# Distance-Sensors.net
KiCad netlist of a schematic drawn in Altium Designer
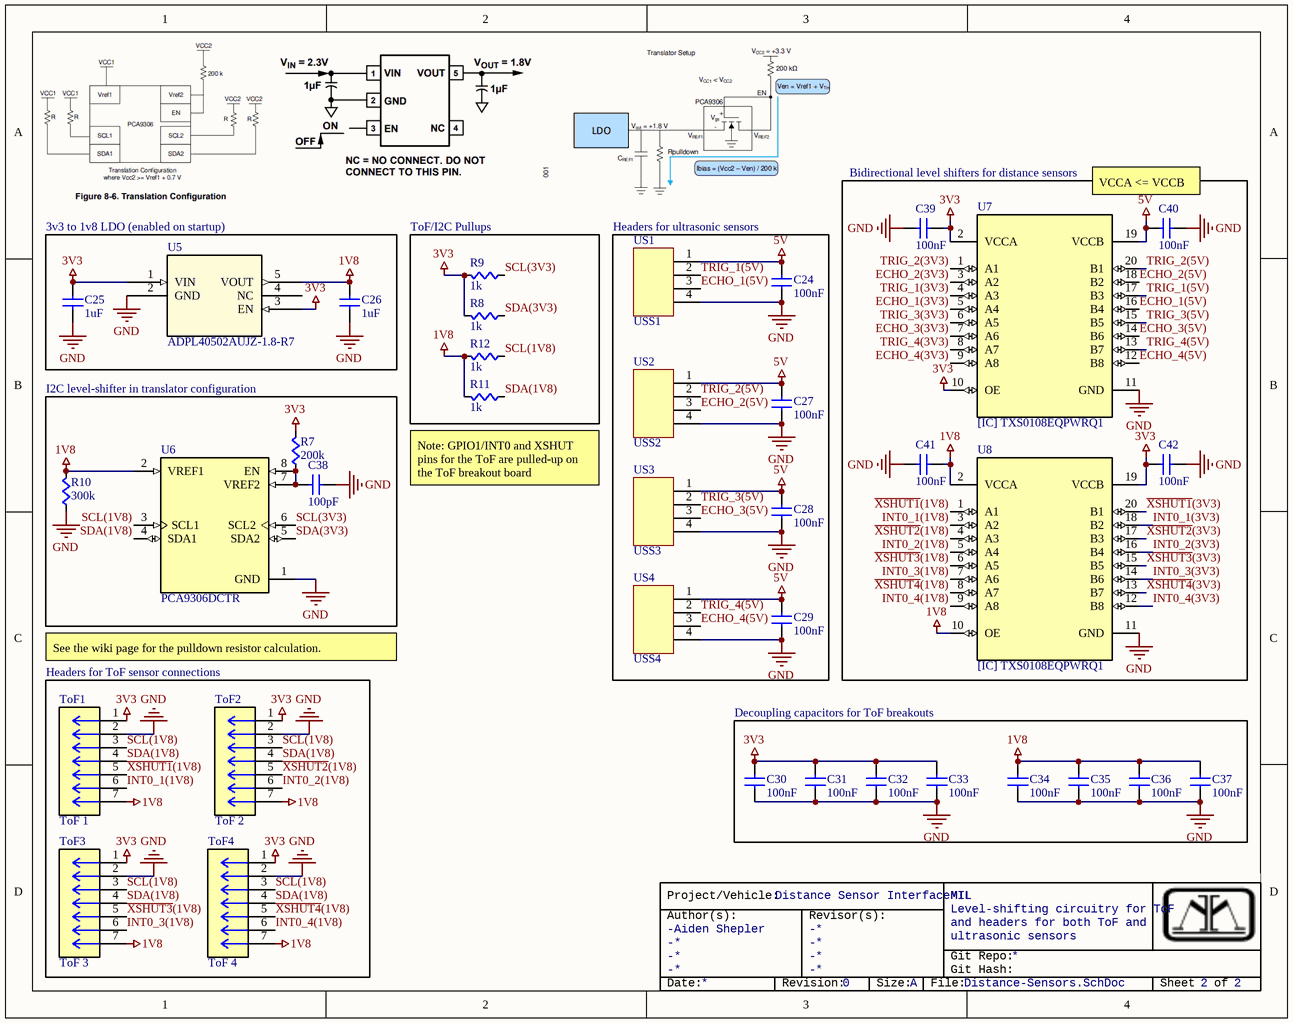
[diagram p0: Distance-Sensors.SchDoc]

(export (version "E")
  (design (tool "Eeschema 10.0.6"))
  (components
    (comp (ref "C24")
      (value "100nF")
      (footprint "CAPC0603")
      (fields (field (name "Comment") "Cap"))
      (libsource (lib "Passives") (part "Cap"))
    )
    (comp (ref "C25")
      (value "1uF")
      (footprint "CAPC0603")
      (fields (field (name "Comment") "Cap"))
      (libsource (lib "Passives") (part "Cap"))
    )
    (comp (ref "C26")
      (value "1uF")
      (footprint "CAPC0603")
      (fields (field (name "Comment") "Cap"))
      (libsource (lib "Passives") (part "Cap"))
    )
    (comp (ref "C27")
      (value "100nF")
      (footprint "CAPC0603")
      (fields (field (name "Comment") "Cap"))
      (libsource (lib "Passives") (part "Cap"))
    )
    (comp (ref "C28")
      (value "100nF")
      (footprint "CAPC0603")
      (fields (field (name "Comment") "Cap"))
      (libsource (lib "Passives") (part "Cap"))
    )
    (comp (ref "C29")
      (value "100nF")
      (footprint "CAPC0603")
      (fields (field (name "Comment") "Cap"))
      (libsource (lib "Passives") (part "Cap"))
    )
    (comp (ref "C30")
      (value "100nF")
      (footprint "CAPC0603")
      (fields (field (name "Comment") "Cap"))
      (libsource (lib "Passives") (part "Cap"))
    )
    (comp (ref "C31")
      (value "100nF")
      (footprint "CAPC0603")
      (fields (field (name "Comment") "Cap"))
      (libsource (lib "Passives") (part "Cap"))
    )
    (comp (ref "C32")
      (value "100nF")
      (footprint "CAPC0603")
      (fields (field (name "Comment") "Cap"))
      (libsource (lib "Passives") (part "Cap"))
    )
    (comp (ref "C33")
      (value "100nF")
      (footprint "CAPC0603")
      (fields (field (name "Comment") "Cap"))
      (libsource (lib "Passives") (part "Cap"))
    )
    (comp (ref "C34")
      (value "100nF")
      (footprint "CAPC0603")
      (fields (field (name "Comment") "Cap"))
      (libsource (lib "Passives") (part "Cap"))
    )
    (comp (ref "C35")
      (value "100nF")
      (footprint "CAPC0603")
      (fields (field (name "Comment") "Cap"))
      (libsource (lib "Passives") (part "Cap"))
    )
    (comp (ref "C36")
      (value "100nF")
      (footprint "CAPC0603")
      (fields (field (name "Comment") "Cap"))
      (libsource (lib "Passives") (part "Cap"))
    )
    (comp (ref "C37")
      (value "100nF")
      (footprint "CAPC0603")
      (fields (field (name "Comment") "Cap"))
      (libsource (lib "Passives") (part "Cap"))
    )
    (comp (ref "C38")
      (value "100pF")
      (footprint "CAPC0603")
      (fields (field (name "Comment") "Cap"))
      (libsource (lib "Passives") (part "Cap"))
    )
    (comp (ref "C39")
      (value "100nF")
      (footprint "CAPC0603")
      (fields (field (name "Comment") "Cap"))
      (libsource (lib "Passives") (part "Cap"))
    )
    (comp (ref "C40")
      (value "100nF")
      (footprint "CAPC0603")
      (fields (field (name "Comment") "Cap"))
      (libsource (lib "Passives") (part "Cap"))
    )
    (comp (ref "C41")
      (value "100nF")
      (footprint "CAPC0603")
      (fields (field (name "Comment") "Cap"))
      (libsource (lib "Passives") (part "Cap"))
    )
    (comp (ref "C42")
      (value "100nF")
      (footprint "CAPC0603")
      (fields (field (name "Comment") "Cap"))
      (libsource (lib "Passives") (part "Cap"))
    )
    (comp (ref "R7")
      (value "200k")
      (footprint "RES0603")
      (description "SMD, RES0603")
      (fields (field (name "Comment") "Res"))
      (libsource (lib "Passives") (part "Res"))
    )
    (comp (ref "R8")
      (value "1k")
      (footprint "RES0603")
      (description "SMD, RES0603")
      (fields (field (name "Comment") "Res"))
      (libsource (lib "Passives") (part "Res"))
    )
    (comp (ref "R9")
      (value "1k")
      (footprint "RES0603")
      (description "SMD, RES0603")
      (fields (field (name "Comment") "Res"))
      (libsource (lib "Passives") (part "Res"))
    )
    (comp (ref "R10")
      (value "300k")
      (footprint "RES0603")
      (description "SMD, RES0603")
      (fields (field (name "Comment") "Res"))
      (libsource (lib "Passives") (part "Res"))
    )
    (comp (ref "R11")
      (value "1k")
      (footprint "RES0603")
      (description "SMD, RES0603")
      (fields (field (name "Comment") "Res"))
      (libsource (lib "Passives") (part "Res"))
    )
    (comp (ref "R12")
      (value "1k")
      (footprint "RES0603")
      (description "SMD, RES0603")
      (fields (field (name "Comment") "Res"))
      (libsource (lib "Passives") (part "Res"))
    )
    (comp (ref "ToF1")
      (value "ToF 1")
      (footprint "7POS_2MM_CONN")
      (description "1x7 2mm pitch sherlock connector")
      (fields (field (name "MP") "353620750"))
      (libsource (lib "353620750") (part "MOLEX_SHERLOCK_1x7_CONN"))
    )
    (comp (ref "ToF2")
      (value "ToF 2")
      (footprint "7POS_2MM_CONN")
      (description "1x7 2mm pitch sherlock connector")
      (fields (field (name "MP") "353620750"))
      (libsource (lib "353620750") (part "MOLEX_SHERLOCK_1x7_CONN"))
    )
    (comp (ref "ToF3")
      (value "ToF 3")
      (footprint "7POS_2MM_CONN")
      (description "1x7 2mm pitch sherlock connector")
      (fields (field (name "MP") "353620750"))
      (libsource (lib "353620750") (part "MOLEX_SHERLOCK_1x7_CONN"))
    )
    (comp (ref "ToF4")
      (value "ToF 4")
      (footprint "7POS_2MM_CONN")
      (description "1x7 2mm pitch sherlock connector")
      (fields (field (name "MP") "353620750"))
      (libsource (lib "353620750") (part "MOLEX_SHERLOCK_1x7_CONN"))
    )
    (comp (ref "U5")
      (value "ADPL40502AUJZ-1.8-R7")
      (footprint "TSOT-23-5_UJ-5_ADI")
      (description "Low Noise, 200mA, CMOS Linear Regulator (LDO)")
      (fields (field (name "COPYRIGHT") "Copyright (C) 2025 Ultra Librarian. All rights reserved."))
      (libsource (lib "Alexandria") (part "ADPL40502AUJZ-1.8-R7"))
    )
    (comp (ref "U6")
      (value "PCA9306DCTR")
      (footprint "SOP65P400X130-8N")
      (description "2-bit bidirectional 400-kHz I2C/SMBus voltage level translator")
      (fields (field (name "MF") "Texas Instruments"))
      (libsource (lib "Alexandria") (part "PCA9306DCTR"))
    )
    (comp (ref "U7")
      (value "[IC] TXS0108EQPWRQ1")
      (footprint "SOP65P640X120-20N")
      (description "Automotive eight-bit bidirectional voltage level shifter for open-drain and push-pull applications")
      (fields (field (name "MF") "Texas Instruments") (field (name "MP") "TXS0108EQPWRQ1"))
      (libsource (lib "Alexandria") (part "[IC] TXS0108EQPWRQ1"))
    )
    (comp (ref "U8")
      (value "[IC] TXS0108EQPWRQ1")
      (footprint "SOP65P640X120-20N")
      (description "Automotive eight-bit bidirectional voltage level shifter for open-drain and push-pull applications")
      (fields (field (name "MF") "Texas Instruments") (field (name "MP") "TXS0108EQPWRQ1"))
      (libsource (lib "Alexandria") (part "[IC] TXS0108EQPWRQ1"))
    )
    (comp (ref "US1")
      (value "USS1")
      (footprint "MOLEX-HDR-1X4-SHERLOCK-VERT")
      (libsource (lib "Connectors") (part "MOLEX-HDR-1x4-SHERLOCK_VERT"))
    )
    (comp (ref "US2")
      (value "USS2")
      (footprint "MOLEX-HDR-1X4-SHERLOCK-VERT")
      (libsource (lib "Connectors") (part "MOLEX-HDR-1x4-SHERLOCK_VERT"))
    )
    (comp (ref "US3")
      (value "USS3")
      (footprint "MOLEX-HDR-1X4-SHERLOCK-VERT")
      (libsource (lib "Connectors") (part "MOLEX-HDR-1x4-SHERLOCK_VERT"))
    )
    (comp (ref "US4")
      (value "USS4")
      (footprint "MOLEX-HDR-1X4-SHERLOCK-VERT")
      (libsource (lib "Connectors") (part "MOLEX-HDR-1x4-SHERLOCK_VERT"))
    )
  )
  (nets
    (net (code "1") (name "/ECHO_1(3V3)") (class "Default")
      (node (ref "U7") (pin "5") (pinfunction "A4_5") (pintype "bidirectional"))
    )
    (net (code "2") (name "/ECHO_1(5V)") (class "Default")
      (node (ref "U7") (pin "16") (pinfunction "B4_16") (pintype "bidirectional"))
      (node (ref "US1") (pin "3") (pinfunction "3_3") (pintype "passive"))
    )
    (net (code "3") (name "/ECHO_2(3V3)") (class "Default")
      (node (ref "U7") (pin "3") (pinfunction "A2_3") (pintype "bidirectional"))
    )
    (net (code "4") (name "/ECHO_2(5V)") (class "Default")
      (node (ref "U7") (pin "18") (pinfunction "B2_18") (pintype "bidirectional"))
      (node (ref "US2") (pin "3") (pinfunction "3_3") (pintype "passive"))
    )
    (net (code "5") (name "/ECHO_3(3V3)") (class "Default")
      (node (ref "U7") (pin "7") (pinfunction "A6_7") (pintype "bidirectional"))
    )
    (net (code "6") (name "/ECHO_3(5V)") (class "Default")
      (node (ref "U7") (pin "14") (pinfunction "B6_14") (pintype "bidirectional"))
      (node (ref "US3") (pin "3") (pinfunction "3_3") (pintype "passive"))
    )
    (net (code "7") (name "/ECHO_4(3V3)") (class "Default")
      (node (ref "U7") (pin "9") (pinfunction "A8_9") (pintype "bidirectional"))
    )
    (net (code "8") (name "/ECHO_4(5V)") (class "Default")
      (node (ref "U7") (pin "12") (pinfunction "B8_12") (pintype "bidirectional"))
      (node (ref "US4") (pin "3") (pinfunction "3_3") (pintype "passive"))
    )
    (net (code "9") (name "/INT0_1(1V8)") (class "Default")
      (node (ref "ToF1") (pin "6") (pinfunction "6_6") (pintype "passive"))
      (node (ref "U8") (pin "3") (pinfunction "A2_3") (pintype "bidirectional"))
    )
    (net (code "10") (name "/INT0_1(3V3)") (class "Default")
      (node (ref "U8") (pin "18") (pinfunction "B2_18") (pintype "bidirectional"))
    )
    (net (code "11") (name "/INT0_2(1V8)") (class "Default")
      (node (ref "ToF2") (pin "6") (pinfunction "6_6") (pintype "passive"))
      (node (ref "U8") (pin "5") (pinfunction "A4_5") (pintype "bidirectional"))
    )
    (net (code "12") (name "/INT0_2(3V3)") (class "Default")
      (node (ref "U8") (pin "16") (pinfunction "B4_16") (pintype "bidirectional"))
    )
    (net (code "13") (name "/INT0_3(1V8)") (class "Default")
      (node (ref "ToF3") (pin "6") (pinfunction "6_6") (pintype "passive"))
      (node (ref "U8") (pin "7") (pinfunction "A6_7") (pintype "bidirectional"))
    )
    (net (code "14") (name "/INT0_3(3V3)") (class "Default")
      (node (ref "U8") (pin "14") (pinfunction "B6_14") (pintype "bidirectional"))
    )
    (net (code "15") (name "/INT0_4(1V8)") (class "Default")
      (node (ref "ToF4") (pin "6") (pinfunction "6_6") (pintype "passive"))
      (node (ref "U8") (pin "9") (pinfunction "A8_9") (pintype "bidirectional"))
    )
    (net (code "16") (name "/INT0_4(3V3)") (class "Default")
      (node (ref "U8") (pin "12") (pinfunction "B8_12") (pintype "bidirectional"))
    )
    (net (code "17") (name "/SCL(1V8)") (class "Default")
      (node (ref "R12") (pin "2") (pinfunction "B_2") (pintype "passive"))
      (node (ref "ToF1") (pin "3") (pinfunction "3_3") (pintype "passive"))
      (node (ref "ToF2") (pin "3") (pinfunction "3_3") (pintype "passive"))
      (node (ref "ToF3") (pin "3") (pinfunction "3_3") (pintype "passive"))
      (node (ref "ToF4") (pin "3") (pinfunction "3_3") (pintype "passive"))
      (node (ref "U6") (pin "3") (pinfunction "SCL1_3") (pintype "input"))
    )
    (net (code "18") (name "/SCL(3V3)") (class "Default")
      (node (ref "R9") (pin "2") (pinfunction "B_2") (pintype "passive"))
      (node (ref "U6") (pin "6") (pinfunction "SCL2_6") (pintype "input"))
    )
    (net (code "19") (name "/SDA(1V8)") (class "Default")
      (node (ref "R11") (pin "2") (pinfunction "B_2") (pintype "passive"))
      (node (ref "ToF1") (pin "4") (pinfunction "4_4") (pintype "passive"))
      (node (ref "ToF2") (pin "4") (pinfunction "4_4") (pintype "passive"))
      (node (ref "ToF3") (pin "4") (pinfunction "4_4") (pintype "passive"))
      (node (ref "ToF4") (pin "4") (pinfunction "4_4") (pintype "passive"))
      (node (ref "U6") (pin "4") (pinfunction "SDA1_4") (pintype "bidirectional"))
    )
    (net (code "20") (name "/SDA(3V3)") (class "Default")
      (node (ref "R8") (pin "2") (pinfunction "B_2") (pintype "passive"))
      (node (ref "U6") (pin "5") (pinfunction "SDA2_5") (pintype "bidirectional"))
    )
    (net (code "21") (name "/TRIG_1(3V3)") (class "Default")
      (node (ref "U7") (pin "4") (pinfunction "A3_4") (pintype "bidirectional"))
    )
    (net (code "22") (name "/TRIG_1(5V)") (class "Default")
      (node (ref "U7") (pin "17") (pinfunction "B3_17") (pintype "bidirectional"))
      (node (ref "US1") (pin "2") (pinfunction "2_2") (pintype "passive"))
    )
    (net (code "23") (name "/TRIG_2(3V3)") (class "Default")
      (node (ref "U7") (pin "1") (pinfunction "A1_1") (pintype "bidirectional"))
    )
    (net (code "24") (name "/TRIG_2(5V)") (class "Default")
      (node (ref "U7") (pin "20") (pinfunction "B1_20") (pintype "bidirectional"))
      (node (ref "US2") (pin "2") (pinfunction "2_2") (pintype "passive"))
    )
    (net (code "25") (name "/TRIG_3(3V3)") (class "Default")
      (node (ref "U7") (pin "6") (pinfunction "A5_6") (pintype "bidirectional"))
    )
    (net (code "26") (name "/TRIG_3(5V)") (class "Default")
      (node (ref "U7") (pin "15") (pinfunction "B5_15") (pintype "bidirectional"))
      (node (ref "US3") (pin "2") (pinfunction "2_2") (pintype "passive"))
    )
    (net (code "27") (name "/TRIG_4(3V3)") (class "Default")
      (node (ref "U7") (pin "8") (pinfunction "A7_8") (pintype "bidirectional"))
    )
    (net (code "28") (name "/TRIG_4(5V)") (class "Default")
      (node (ref "U7") (pin "13") (pinfunction "B7_13") (pintype "bidirectional"))
      (node (ref "US4") (pin "2") (pinfunction "2_2") (pintype "passive"))
    )
    (net (code "29") (name "/~{XSHUT1}(1V8)") (class "Default")
      (node (ref "ToF1") (pin "5") (pinfunction "5_5") (pintype "passive"))
      (node (ref "U8") (pin "1") (pinfunction "A1_1") (pintype "bidirectional"))
    )
    (net (code "30") (name "/~{XSHUT1}(3V3)") (class "Default")
      (node (ref "U8") (pin "20") (pinfunction "B1_20") (pintype "bidirectional"))
    )
    (net (code "31") (name "/~{XSHUT2}(1V8)") (class "Default")
      (node (ref "ToF2") (pin "5") (pinfunction "5_5") (pintype "passive"))
      (node (ref "U8") (pin "4") (pinfunction "A3_4") (pintype "bidirectional"))
    )
    (net (code "32") (name "/~{XSHUT2}(3V3)") (class "Default")
      (node (ref "U8") (pin "17") (pinfunction "B3_17") (pintype "bidirectional"))
    )
    (net (code "33") (name "/~{XSHUT3}(1V8)") (class "Default")
      (node (ref "ToF3") (pin "5") (pinfunction "5_5") (pintype "passive"))
      (node (ref "U8") (pin "6") (pinfunction "A5_6") (pintype "bidirectional"))
    )
    (net (code "34") (name "/~{XSHUT3}(3V3)") (class "Default")
      (node (ref "U8") (pin "15") (pinfunction "B5_15") (pintype "bidirectional"))
    )
    (net (code "35") (name "/~{XSHUT4}(1V8)") (class "Default")
      (node (ref "ToF4") (pin "5") (pinfunction "5_5") (pintype "passive"))
      (node (ref "U8") (pin "8") (pinfunction "A7_8") (pintype "bidirectional"))
    )
    (net (code "36") (name "/~{XSHUT4}(3V3)") (class "Default")
      (node (ref "U8") (pin "13") (pinfunction "B7_13") (pintype "bidirectional"))
    )
    (net (code "37") (name "1V8") (class "Default")
      (node (ref "C26") (pin "1") (pinfunction "A_1") (pintype "passive"))
      (node (ref "C34") (pin "1") (pinfunction "A_1") (pintype "passive"))
      (node (ref "C35") (pin "1") (pinfunction "A_1") (pintype "passive"))
      (node (ref "C36") (pin "1") (pinfunction "A_1") (pintype "passive"))
      (node (ref "C37") (pin "1") (pinfunction "A_1") (pintype "passive"))
      (node (ref "C41") (pin "2") (pinfunction "B_2") (pintype "passive"))
      (node (ref "R10") (pin "1") (pinfunction "A_1") (pintype "passive"))
      (node (ref "R11") (pin "1") (pinfunction "A_1") (pintype "passive"))
      (node (ref "R12") (pin "1") (pinfunction "A_1") (pintype "passive"))
      (node (ref "ToF1") (pin "7") (pinfunction "7_7") (pintype "passive"))
      (node (ref "ToF2") (pin "7") (pinfunction "7_7") (pintype "passive"))
      (node (ref "ToF3") (pin "7") (pinfunction "7_7") (pintype "passive"))
      (node (ref "ToF4") (pin "7") (pinfunction "7_7") (pintype "passive"))
      (node (ref "U5") (pin "5") (pinfunction "VOUT_5") (pintype "output"))
      (node (ref "U6") (pin "2") (pinfunction "VREF1_2") (pintype "input"))
      (node (ref "U8") (pin "10") (pinfunction "OE_10") (pintype "bidirectional"))
      (node (ref "U8") (pin "2") (pinfunction "VCCA_2") (pintype "power_in"))
    )
    (net (code "38") (name "3V3") (class "Default")
      (node (ref "C25") (pin "1") (pinfunction "A_1") (pintype "passive"))
      (node (ref "C30") (pin "1") (pinfunction "A_1") (pintype "passive"))
      (node (ref "C31") (pin "1") (pinfunction "A_1") (pintype "passive"))
      (node (ref "C32") (pin "1") (pinfunction "A_1") (pintype "passive"))
      (node (ref "C33") (pin "1") (pinfunction "A_1") (pintype "passive"))
      (node (ref "C39") (pin "2") (pinfunction "B_2") (pintype "passive"))
      (node (ref "C42") (pin "2") (pinfunction "B_2") (pintype "passive"))
      (node (ref "R7") (pin "1") (pinfunction "A_1") (pintype "passive"))
      (node (ref "R8") (pin "1") (pinfunction "A_1") (pintype "passive"))
      (node (ref "R9") (pin "1") (pinfunction "A_1") (pintype "passive"))
      (node (ref "ToF1") (pin "1") (pinfunction "1_1") (pintype "passive"))
      (node (ref "ToF2") (pin "1") (pinfunction "1_1") (pintype "passive"))
      (node (ref "ToF3") (pin "1") (pinfunction "1_1") (pintype "passive"))
      (node (ref "ToF4") (pin "1") (pinfunction "1_1") (pintype "passive"))
      (node (ref "U5") (pin "1") (pinfunction "VIN_1") (pintype "input"))
      (node (ref "U5") (pin "3") (pinfunction "EN_3") (pintype "input"))
      (node (ref "U7") (pin "10") (pinfunction "OE_10") (pintype "bidirectional"))
      (node (ref "U7") (pin "2") (pinfunction "VCCA_2") (pintype "power_in"))
      (node (ref "U8") (pin "19") (pinfunction "VCCB_19") (pintype "power_in"))
    )
    (net (code "39") (name "5V") (class "Default")
      (node (ref "C24") (pin "1") (pinfunction "A_1") (pintype "passive"))
      (node (ref "C27") (pin "1") (pinfunction "A_1") (pintype "passive"))
      (node (ref "C28") (pin "1") (pinfunction "A_1") (pintype "passive"))
      (node (ref "C29") (pin "1") (pinfunction "A_1") (pintype "passive"))
      (node (ref "C40") (pin "1") (pinfunction "A_1") (pintype "passive"))
      (node (ref "U7") (pin "19") (pinfunction "VCCB_19") (pintype "power_in"))
      (node (ref "US1") (pin "1") (pinfunction "1_1") (pintype "passive"))
      (node (ref "US2") (pin "1") (pinfunction "1_1") (pintype "passive"))
      (node (ref "US3") (pin "1") (pinfunction "1_1") (pintype "passive"))
      (node (ref "US4") (pin "1") (pinfunction "1_1") (pintype "passive"))
    )
    (net (code "40") (name "GND") (class "Default")
      (node (ref "C24") (pin "2") (pinfunction "B_2") (pintype "passive"))
      (node (ref "C25") (pin "2") (pinfunction "B_2") (pintype "passive"))
      (node (ref "C26") (pin "2") (pinfunction "B_2") (pintype "passive"))
      (node (ref "C27") (pin "2") (pinfunction "B_2") (pintype "passive"))
      (node (ref "C28") (pin "2") (pinfunction "B_2") (pintype "passive"))
      (node (ref "C29") (pin "2") (pinfunction "B_2") (pintype "passive"))
      (node (ref "C30") (pin "2") (pinfunction "B_2") (pintype "passive"))
      (node (ref "C31") (pin "2") (pinfunction "B_2") (pintype "passive"))
      (node (ref "C32") (pin "2") (pinfunction "B_2") (pintype "passive"))
      (node (ref "C33") (pin "2") (pinfunction "B_2") (pintype "passive"))
      (node (ref "C34") (pin "2") (pinfunction "B_2") (pintype "passive"))
      (node (ref "C35") (pin "2") (pinfunction "B_2") (pintype "passive"))
      (node (ref "C36") (pin "2") (pinfunction "B_2") (pintype "passive"))
      (node (ref "C37") (pin "2") (pinfunction "B_2") (pintype "passive"))
      (node (ref "C38") (pin "2") (pinfunction "B_2") (pintype "passive"))
      (node (ref "C39") (pin "1") (pinfunction "A_1") (pintype "passive"))
      (node (ref "C40") (pin "2") (pinfunction "B_2") (pintype "passive"))
      (node (ref "C41") (pin "1") (pinfunction "A_1") (pintype "passive"))
      (node (ref "C42") (pin "1") (pinfunction "A_1") (pintype "passive"))
      (node (ref "R10") (pin "2") (pinfunction "B_2") (pintype "passive"))
      (node (ref "ToF1") (pin "2") (pinfunction "2_2") (pintype "passive"))
      (node (ref "ToF2") (pin "2") (pinfunction "2_2") (pintype "passive"))
      (node (ref "ToF3") (pin "2") (pinfunction "2_2") (pintype "passive"))
      (node (ref "ToF4") (pin "2") (pinfunction "2_2") (pintype "passive"))
      (node (ref "U5") (pin "2") (pinfunction "GND_2") (pintype "power_in"))
      (node (ref "U6") (pin "1") (pinfunction "GND_1") (pintype "power_in"))
      (node (ref "U7") (pin "11") (pinfunction "GND_11") (pintype "power_in"))
      (node (ref "U8") (pin "11") (pinfunction "GND_11") (pintype "power_in"))
      (node (ref "US1") (pin "4") (pinfunction "4_4") (pintype "passive"))
      (node (ref "US2") (pin "4") (pinfunction "4_4") (pintype "passive"))
      (node (ref "US3") (pin "4") (pinfunction "4_4") (pintype "passive"))
      (node (ref "US4") (pin "4") (pinfunction "4_4") (pintype "passive"))
    )
    (net (code "41") (name "Net-(C38-A)") (class "Default")
      (node (ref "C38") (pin "1") (pinfunction "A_1") (pintype "passive"))
      (node (ref "R7") (pin "2") (pinfunction "B_2") (pintype "passive"))
      (node (ref "U6") (pin "7") (pinfunction "VREF2_7") (pintype "input"))
      (node (ref "U6") (pin "8") (pinfunction "EN_8") (pintype "input"))
    )
    (net (code "42") (name "unconnected-(U5-NC-Pad4)") (class "Default")
      (node (ref "U5") (pin "4") (pinfunction "NC_4") (pintype "passive"))
    )
  )
)
